# MI_04_05.net
KiCad netlist of a schematic drawn in Altium Designer
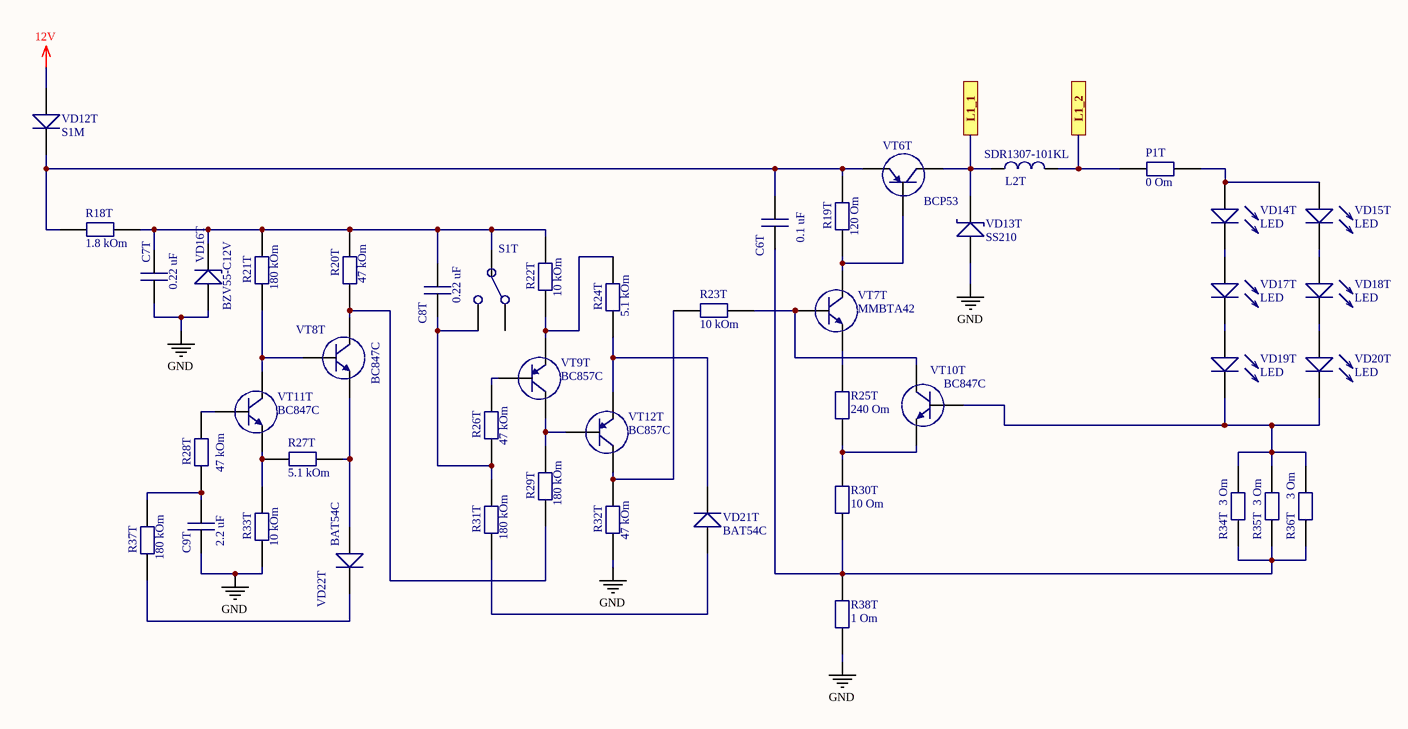
[diagram p0: MI_04_05.SchDoc]

(export (version "E")
  (design (tool "Eeschema 10.0.6"))
  (components
    (comp (ref "C6T")
      (value "0.1 uF")
      (footprint "CAP1206")
      (fields (field (name "Comment") "Capacitor"))
      (libsource (lib "my_library") (part "Capacitor"))
    )
    (comp (ref "C7T")
      (value "0.22 uF")
      (footprint "CAP1206")
      (fields (field (name "Comment") "Capacitor"))
      (libsource (lib "my_library") (part "Capacitor"))
    )
    (comp (ref "C8T")
      (value "0.22 uF")
      (footprint "CAP1206")
      (fields (field (name "Comment") "Capacitor"))
      (libsource (lib "my_library") (part "Capacitor"))
    )
    (comp (ref "C9T")
      (value "2.2 uF")
      (footprint "CAP1206")
      (fields (field (name "Comment") "Capacitor"))
      (libsource (lib "my_library") (part "Capacitor"))
    )
    (comp (ref "L2T")
      (value "SDR1307-101KL")
      (footprint "SDR1307")
      (fields (field (name "Comment") "coil"))
      (libsource (lib "my_library") (part "coil"))
    )
    (comp (ref "P1T")
      (value "0 Om")
      (footprint "RES1206")
      (fields (field (name "Comment") "Resistor"))
      (libsource (lib "my_library") (part "Resistor"))
    )
    (comp (ref "R18T")
      (value "1.8 kOm")
      (footprint "RES1206")
      (fields (field (name "Comment") "Resistor"))
      (libsource (lib "my_library") (part "Resistor"))
    )
    (comp (ref "R19T")
      (value "120 Om")
      (footprint "RES1206")
      (fields (field (name "Comment") "Resistor"))
      (libsource (lib "my_library") (part "Resistor"))
    )
    (comp (ref "R20T")
      (value "47 kOm")
      (footprint "RES1206")
      (fields (field (name "Comment") "Resistor"))
      (libsource (lib "my_library") (part "Resistor"))
    )
    (comp (ref "R21T")
      (value "180 kOm")
      (footprint "RES1206")
      (fields (field (name "Comment") "Resistor"))
      (libsource (lib "my_library") (part "Resistor"))
    )
    (comp (ref "R22T")
      (value "10 kOm")
      (footprint "RES1206")
      (fields (field (name "Comment") "Resistor"))
      (libsource (lib "my_library") (part "Resistor"))
    )
    (comp (ref "R23T")
      (value "10 kOm")
      (footprint "RES1206")
      (fields (field (name "Comment") "Resistor"))
      (libsource (lib "my_library") (part "Resistor"))
    )
    (comp (ref "R24T")
      (value "5.1 kOm")
      (footprint "RES1206")
      (fields (field (name "Comment") "Resistor"))
      (libsource (lib "my_library") (part "Resistor"))
    )
    (comp (ref "R25T")
      (value "240 Om")
      (footprint "RES1206")
      (fields (field (name "Comment") "Resistor"))
      (libsource (lib "my_library") (part "Resistor"))
    )
    (comp (ref "R26T")
      (value "47 kOm")
      (footprint "RES1206")
      (fields (field (name "Comment") "Resistor"))
      (libsource (lib "my_library") (part "Resistor"))
    )
    (comp (ref "R27T")
      (value "5.1 kOm")
      (footprint "RES1206")
      (fields (field (name "Comment") "Resistor"))
      (libsource (lib "my_library") (part "Resistor"))
    )
    (comp (ref "R28T")
      (value "47 kOm")
      (footprint "RES1206")
      (fields (field (name "Comment") "Resistor"))
      (libsource (lib "my_library") (part "Resistor"))
    )
    (comp (ref "R29T")
      (value "180 kOm")
      (footprint "RES1206")
      (fields (field (name "Comment") "Resistor"))
      (libsource (lib "my_library") (part "Resistor"))
    )
    (comp (ref "R30T")
      (value "10 Om")
      (footprint "RES1206")
      (fields (field (name "Comment") "Resistor"))
      (libsource (lib "my_library") (part "Resistor"))
    )
    (comp (ref "R31T")
      (value "180 kOm")
      (footprint "RES1206")
      (fields (field (name "Comment") "Resistor"))
      (libsource (lib "my_library") (part "Resistor"))
    )
    (comp (ref "R32T")
      (value "47 kOm")
      (footprint "RES1206")
      (fields (field (name "Comment") "Resistor"))
      (libsource (lib "my_library") (part "Resistor"))
    )
    (comp (ref "R33T")
      (value "10 kOm")
      (footprint "RES1206")
      (fields (field (name "Comment") "Resistor"))
      (libsource (lib "my_library") (part "Resistor"))
    )
    (comp (ref "R34T")
      (value "3 Om")
      (footprint "RES1206")
      (fields (field (name "Comment") "Resistor"))
      (libsource (lib "my_library") (part "Resistor"))
    )
    (comp (ref "R35T")
      (value "3 Om")
      (footprint "RES1206")
      (fields (field (name "Comment") "Resistor"))
      (libsource (lib "my_library") (part "Resistor"))
    )
    (comp (ref "R36T")
      (value "3 Om")
      (footprint "RES1206")
      (fields (field (name "Comment") "Resistor"))
      (libsource (lib "my_library") (part "Resistor"))
    )
    (comp (ref "R37T")
      (value "180 kOm")
      (footprint "RES1206")
      (fields (field (name "Comment") "Resistor"))
      (libsource (lib "my_library") (part "Resistor"))
    )
    (comp (ref "R38T")
      (value "1 Om")
      (footprint "RES1206")
      (fields (field (name "Comment") "Resistor"))
      (libsource (lib "my_library") (part "Resistor"))
    )
    (comp (ref "S1T")
      (value "~")
      (footprint "Solder_connector")
      (libsource (lib "my_library") (part "switch"))
    )
    (comp (ref "VD12T")
      (value "S1M")
      (footprint "SMA-F")
      (fields (field (name "Comment") "Diode"))
      (libsource (lib "my_library") (part "Diode"))
    )
    (comp (ref "VD13T")
      (value "SS210")
      (footprint "SMB1")
      (fields (field (name "Comment") "Schottky"))
      (libsource (lib "my_library") (part "Schottky"))
    )
    (comp (ref "VD14T") (value "LED") (footprint "LED_MAJAK") (libsource (lib "my_library") (part "LED")))
    (comp (ref "VD15T") (value "LED") (footprint "LED_MAJAK") (libsource (lib "my_library") (part "LED")))
    (comp (ref "VD16T")
      (value "BZV55-C12V")
      (footprint "minimelf")
      (fields (field (name "Comment") "Zenner"))
      (libsource (lib "my_library") (part "Zenner"))
    )
    (comp (ref "VD17T") (value "LED") (footprint "LED_MAJAK") (libsource (lib "my_library") (part "LED")))
    (comp (ref "VD18T") (value "LED") (footprint "LED_MAJAK") (libsource (lib "my_library") (part "LED")))
    (comp (ref "VD19T") (value "LED") (footprint "LED_MAJAK") (libsource (lib "my_library") (part "LED")))
    (comp (ref "VD20T") (value "LED") (footprint "LED_MAJAK") (libsource (lib "my_library") (part "LED")))
    (comp (ref "VD21T")
      (value "BAT54C")
      (footprint "SOT 23")
      (fields (field (name "Comment") "Diode"))
      (libsource (lib "my_library") (part "Diode"))
    )
    (comp (ref "VD22T")
      (value "BAT54C")
      (footprint "SOT 23")
      (fields (field (name "Comment") "Diode"))
      (libsource (lib "my_library") (part "Diode"))
    )
    (comp (ref "VT6T")
      (value "BCP53")
      (footprint "SOT223")
      (fields (field (name "Comment") "PNP"))
      (libsource (lib "") (part "PNP_1"))
    )
    (comp (ref "VT7T")
      (value "MMBTA42")
      (footprint "SOT 23")
      (fields (field (name "Comment") "NPN"))
      (libsource (lib "my_library") (part "NPN"))
    )
    (comp (ref "VT8T")
      (value "BC847C")
      (footprint "SOT 23")
      (fields (field (name "Comment") "NPN"))
      (libsource (lib "my_library") (part "NPN"))
    )
    (comp (ref "VT9T")
      (value "BC857C")
      (footprint "SOT 23")
      (fields (field (name "Comment") "PNP"))
      (libsource (lib "my_library") (part "PNP"))
    )
    (comp (ref "VT10T")
      (value "BC847C")
      (footprint "SOT 23")
      (fields (field (name "Comment") "NPN"))
      (libsource (lib "") (part "NPN_1"))
    )
    (comp (ref "VT11T")
      (value "BC847C")
      (footprint "SOT 23")
      (fields (field (name "Comment") "NPN"))
      (libsource (lib "my_library") (part "NPN"))
    )
    (comp (ref "VT12T")
      (value "BC857C")
      (footprint "SOT 23")
      (fields (field (name "Comment") "PNP"))
      (libsource (lib "my_library") (part "PNP"))
    )
  )
  (nets
    (net (code "1") (name "/L1_1") (class "Default")
      (node (ref "L2T") (pin "1") (pinfunction "1_1") (pintype "passive"))
      (node (ref "VD13T") (pin "1") (pinfunction "1_1") (pintype "passive"))
      (node (ref "VT6T") (pin "K") (pinfunction "K_K") (pintype "passive"))
    )
    (net (code "2") (name "/L1_2") (class "Default")
      (node (ref "L2T") (pin "2") (pinfunction "2_2") (pintype "passive"))
      (node (ref "P1T") (pin "1") (pinfunction "1_1") (pintype "passive"))
    )
    (net (code "3") (name "12V") (class "Default")
      (node (ref "VD12T") (pin "2") (pinfunction "2_2") (pintype "passive"))
    )
    (net (code "4") (name "GND") (class "Default")
      (node (ref "C7T") (pin "1") (pinfunction "1_1") (pintype "passive"))
      (node (ref "C9T") (pin "1") (pinfunction "1_1") (pintype "passive"))
      (node (ref "R32T") (pin "2") (pinfunction "2_2") (pintype "passive"))
      (node (ref "R33T") (pin "2") (pinfunction "2_2") (pintype "passive"))
      (node (ref "R38T") (pin "1") (pinfunction "1_1") (pintype "passive"))
      (node (ref "VD13T") (pin "2") (pinfunction "2_2") (pintype "passive"))
      (node (ref "VD16T") (pin "2") (pinfunction "2_2") (pintype "passive"))
    )
    (net (code "5") (name "Net-(C6T-Pad1)") (class "Default")
      (node (ref "C6T") (pin "1") (pinfunction "1_1") (pintype "passive"))
      (node (ref "R30T") (pin "1") (pinfunction "1_1") (pintype "passive"))
      (node (ref "R34T") (pin "1") (pinfunction "1_1") (pintype "passive"))
      (node (ref "R35T") (pin "1") (pinfunction "1_1") (pintype "passive"))
      (node (ref "R36T") (pin "1") (pinfunction "1_1") (pintype "passive"))
      (node (ref "R38T") (pin "2") (pinfunction "2_2") (pintype "passive"))
    )
    (net (code "6") (name "Net-(C6T-Pad2)") (class "Default")
      (node (ref "C6T") (pin "2") (pinfunction "2_2") (pintype "passive"))
      (node (ref "R18T") (pin "2") (pinfunction "2_2") (pintype "passive"))
      (node (ref "R19T") (pin "1") (pinfunction "1_1") (pintype "passive"))
      (node (ref "VD12T") (pin "1") (pinfunction "1_1") (pintype "passive"))
      (node (ref "VT6T") (pin "E") (pinfunction "E_E") (pintype "passive"))
    )
    (net (code "7") (name "Net-(C7T-Pad2)") (class "Default")
      (node (ref "C7T") (pin "2") (pinfunction "2_2") (pintype "passive"))
      (node (ref "C8T") (pin "2") (pinfunction "2_2") (pintype "passive"))
      (node (ref "R18T") (pin "1") (pinfunction "1_1") (pintype "passive"))
      (node (ref "R20T") (pin "1") (pinfunction "1_1") (pintype "passive"))
      (node (ref "R21T") (pin "1") (pinfunction "1_1") (pintype "passive"))
      (node (ref "R22T") (pin "1") (pinfunction "1_1") (pintype "passive"))
      (node (ref "S1T") (pin "1") (pinfunction "1_1") (pintype "passive"))
      (node (ref "VD16T") (pin "1") (pinfunction "1_1") (pintype "passive"))
    )
    (net (code "8") (name "Net-(C8T-Pad1)") (class "Default")
      (node (ref "C8T") (pin "1") (pinfunction "1_1") (pintype "passive"))
      (node (ref "R26T") (pin "2") (pinfunction "2_2") (pintype "passive"))
      (node (ref "R31T") (pin "1") (pinfunction "1_1") (pintype "passive"))
      (node (ref "S1T") (pin "2") (pinfunction "2_2") (pintype "passive"))
    )
    (net (code "9") (name "Net-(C9T-Pad2)") (class "Default")
      (node (ref "C9T") (pin "2") (pinfunction "2_2") (pintype "passive"))
      (node (ref "R28T") (pin "2") (pinfunction "2_2") (pintype "passive"))
      (node (ref "R37T") (pin "1") (pinfunction "1_1") (pintype "passive"))
    )
    (net (code "10") (name "Net-(P1T-Pad2)") (class "Default")
      (node (ref "P1T") (pin "2") (pinfunction "2_2") (pintype "passive"))
      (node (ref "VD14T") (pin "2") (pinfunction "2_2") (pintype "passive"))
      (node (ref "VD15T") (pin "2") (pinfunction "2_2") (pintype "passive"))
    )
    (net (code "11") (name "Net-(R19T-Pad2)") (class "Default")
      (node (ref "R19T") (pin "2") (pinfunction "2_2") (pintype "passive"))
      (node (ref "VT6T") (pin "B") (pinfunction "B_B") (pintype "passive"))
      (node (ref "VT7T") (pin "K") (pinfunction "K_K") (pintype "passive"))
    )
    (net (code "12") (name "Net-(R20T-Pad2)") (class "Default")
      (node (ref "R20T") (pin "2") (pinfunction "2_2") (pintype "passive"))
      (node (ref "R29T") (pin "2") (pinfunction "2_2") (pintype "passive"))
      (node (ref "VT8T") (pin "K") (pinfunction "K_K") (pintype "passive"))
    )
    (net (code "13") (name "Net-(R21T-Pad2)") (class "Default")
      (node (ref "R21T") (pin "2") (pinfunction "2_2") (pintype "passive"))
      (node (ref "VT11T") (pin "K") (pinfunction "K_K") (pintype "passive"))
      (node (ref "VT8T") (pin "B") (pinfunction "B_B") (pintype "passive"))
    )
    (net (code "14") (name "Net-(R22T-Pad2)") (class "Default")
      (node (ref "R22T") (pin "2") (pinfunction "2_2") (pintype "passive"))
      (node (ref "R24T") (pin "1") (pinfunction "1_1") (pintype "passive"))
      (node (ref "VT9T") (pin "E") (pinfunction "E_E") (pintype "passive"))
    )
    (net (code "15") (name "Net-(R23T-Pad1)") (class "Default")
      (node (ref "R23T") (pin "1") (pinfunction "1_1") (pintype "passive"))
      (node (ref "R32T") (pin "1") (pinfunction "1_1") (pintype "passive"))
      (node (ref "VT12T") (pin "K") (pinfunction "K_K") (pintype "passive"))
    )
    (net (code "16") (name "Net-(R23T-Pad2)") (class "Default")
      (node (ref "R23T") (pin "2") (pinfunction "2_2") (pintype "passive"))
      (node (ref "VT10T") (pin "K") (pinfunction "K_K") (pintype "passive"))
      (node (ref "VT7T") (pin "B") (pinfunction "B_B") (pintype "passive"))
    )
    (net (code "17") (name "Net-(R24T-Pad2)") (class "Default")
      (node (ref "R24T") (pin "2") (pinfunction "2_2") (pintype "passive"))
      (node (ref "VD21T") (pin "1") (pinfunction "1_1") (pintype "passive"))
      (node (ref "VT12T") (pin "E") (pinfunction "E_E") (pintype "passive"))
    )
    (net (code "18") (name "Net-(R25T-Pad1)") (class "Default")
      (node (ref "R25T") (pin "1") (pinfunction "1_1") (pintype "passive"))
      (node (ref "R30T") (pin "2") (pinfunction "2_2") (pintype "passive"))
      (node (ref "VT10T") (pin "E") (pinfunction "E_E") (pintype "passive"))
    )
    (net (code "19") (name "Net-(R25T-Pad2)") (class "Default")
      (node (ref "R25T") (pin "2") (pinfunction "2_2") (pintype "passive"))
      (node (ref "VT7T") (pin "E") (pinfunction "E_E") (pintype "passive"))
    )
    (net (code "20") (name "Net-(R26T-Pad1)") (class "Default")
      (node (ref "R26T") (pin "1") (pinfunction "1_1") (pintype "passive"))
      (node (ref "VT9T") (pin "B") (pinfunction "B_B") (pintype "passive"))
    )
    (net (code "21") (name "Net-(R27T-Pad1)") (class "Default")
      (node (ref "R27T") (pin "1") (pinfunction "1_1") (pintype "passive"))
      (node (ref "VD22T") (pin "2") (pinfunction "2_2") (pintype "passive"))
      (node (ref "VT8T") (pin "E") (pinfunction "E_E") (pintype "passive"))
    )
    (net (code "22") (name "Net-(R27T-Pad2)") (class "Default")
      (node (ref "R27T") (pin "2") (pinfunction "2_2") (pintype "passive"))
      (node (ref "R33T") (pin "1") (pinfunction "1_1") (pintype "passive"))
      (node (ref "VT11T") (pin "E") (pinfunction "E_E") (pintype "passive"))
    )
    (net (code "23") (name "Net-(R28T-Pad1)") (class "Default")
      (node (ref "R28T") (pin "1") (pinfunction "1_1") (pintype "passive"))
      (node (ref "VT11T") (pin "B") (pinfunction "B_B") (pintype "passive"))
    )
    (net (code "24") (name "Net-(R29T-Pad1)") (class "Default")
      (node (ref "R29T") (pin "1") (pinfunction "1_1") (pintype "passive"))
      (node (ref "VT12T") (pin "B") (pinfunction "B_B") (pintype "passive"))
      (node (ref "VT9T") (pin "K") (pinfunction "K_K") (pintype "passive"))
    )
    (net (code "25") (name "Net-(R31T-Pad2)") (class "Default")
      (node (ref "R31T") (pin "2") (pinfunction "2_2") (pintype "passive"))
      (node (ref "VD21T") (pin "2") (pinfunction "2_2") (pintype "passive"))
    )
    (net (code "26") (name "Net-(R34T-Pad2)") (class "Default")
      (node (ref "R34T") (pin "2") (pinfunction "2_2") (pintype "passive"))
      (node (ref "R35T") (pin "2") (pinfunction "2_2") (pintype "passive"))
      (node (ref "R36T") (pin "2") (pinfunction "2_2") (pintype "passive"))
      (node (ref "VD19T") (pin "1") (pinfunction "1_1") (pintype "passive"))
      (node (ref "VD20T") (pin "1") (pinfunction "1_1") (pintype "passive"))
      (node (ref "VT10T") (pin "B") (pinfunction "B_B") (pintype "passive"))
    )
    (net (code "27") (name "Net-(R37T-Pad2)") (class "Default")
      (node (ref "R37T") (pin "2") (pinfunction "2_2") (pintype "passive"))
      (node (ref "VD22T") (pin "1") (pinfunction "1_1") (pintype "passive"))
    )
    (net (code "28") (name "Net-(VD14T-Pad1)") (class "Default")
      (node (ref "VD14T") (pin "1") (pinfunction "1_1") (pintype "passive"))
      (node (ref "VD17T") (pin "2") (pinfunction "2_2") (pintype "passive"))
    )
    (net (code "29") (name "Net-(VD15T-Pad1)") (class "Default")
      (node (ref "VD15T") (pin "1") (pinfunction "1_1") (pintype "passive"))
      (node (ref "VD18T") (pin "2") (pinfunction "2_2") (pintype "passive"))
    )
    (net (code "30") (name "Net-(VD17T-Pad1)") (class "Default")
      (node (ref "VD17T") (pin "1") (pinfunction "1_1") (pintype "passive"))
      (node (ref "VD19T") (pin "2") (pinfunction "2_2") (pintype "passive"))
    )
    (net (code "31") (name "Net-(VD18T-Pad1)") (class "Default")
      (node (ref "VD18T") (pin "1") (pinfunction "1_1") (pintype "passive"))
      (node (ref "VD20T") (pin "2") (pinfunction "2_2") (pintype "passive"))
    )
    (net (code "32") (name "unconnected-(S1T-Pad3)") (class "Default")
      (node (ref "S1T") (pin "3") (pinfunction "3_3") (pintype "passive"))
    )
  )
)
